# PIC.net
KiCad netlist of a schematic drawn in Altium Designer
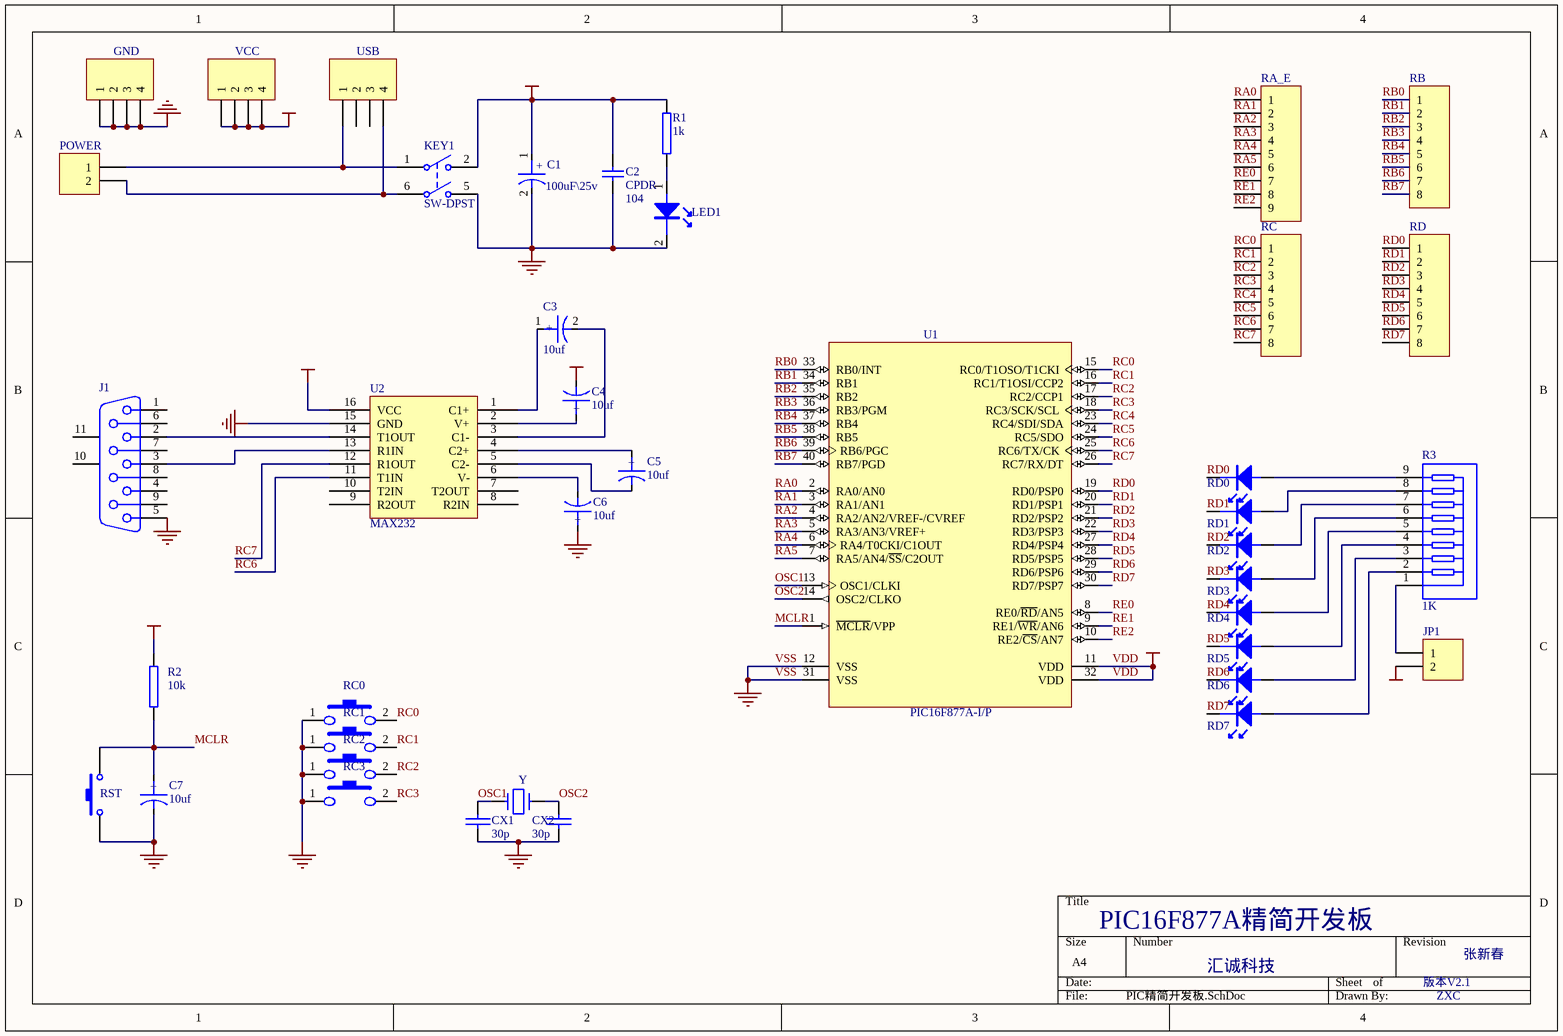
[diagram p0: PIC精简开发板.SchDoc]

(export (version "E")
  (design (tool "Eeschema 10.0.6"))
  (components
    (comp (ref "C1")
      (value "100u~{F}25v")
      (footprint "C-DJ-6")
      (description "Capacitor")
      (libsource (lib "OldCow1 (1)") (part "CAPACITOR POL"))
    )
    (comp (ref "C2")
      (value "CPDR")
      (footprint "CPDR")
      (description "瓷片电容")
      (fields (field (name "ALTIUM_VALUE") "104") (field (name "PUBLISHER") "Altium Limited"))
      (libsource (lib "zxcourhc") (part "CPDR"))
    )
    (comp (ref "C3")
      (value "10uf")
      (footprint "C-DJ-4")
      (description "Capacitor")
      (libsource (lib "") (part "CAPACITOR POL_1"))
    )
    (comp (ref "C4")
      (value "10uf")
      (footprint "C-DJ-4")
      (description "Capacitor")
      (libsource (lib "*") (part "CAPACITOR POL"))
    )
    (comp (ref "C5")
      (value "10uf")
      (footprint "C-DJ-4")
      (description "Capacitor")
      (libsource (lib "*") (part "CAPACITOR POL"))
    )
    (comp (ref "C6")
      (value "10uf")
      (footprint "C-DJ-4")
      (description "Capacitor")
      (libsource (lib "*") (part "CAPACITOR POL"))
    )
    (comp (ref "C7")
      (value "10uf")
      (footprint "C-DJ-4")
      (description "Capacitor")
      (libsource (lib "*") (part "CAPACITOR POL"))
    )
    (comp (ref "CX1")
      (value "30p")
      (footprint "HDR1X2")
      (description "Capacitor")
      (libsource (lib "*") (part "CAP"))
    )
    (comp (ref "CX2")
      (value "30p")
      (footprint "HDR1X2")
      (description "Capacitor")
      (libsource (lib "*") (part "CAP"))
    )
    (comp (ref "GND")
      (value "~")
      (footprint "HDR1X4")
      (description "Header, 4-Pin")
      (fields (field (name "PUBLISHER") "Altium Limited"))
      (libsource (lib "Miscellaneous Connectors") (part "Header 4"))
    )
    (comp (ref "J1")
      (value "D Connector 9")
      (footprint "DSUB1.385-2H9")
      (description "Receptacle Assembly, 9 Position, Right Angle")
      (fields (field (name "PUBLISHER") "Altium Limited"))
      (libsource (lib "Miscellaneous Connectors") (part "D Connector 9"))
    )
    (comp (ref "JP1")
      (value "~")
      (footprint "HDR1X2")
      (description "Header, 2-Pin")
      (fields (field (name "PUBLISHER") "Altium Limited"))
      (libsource (lib "") (part "Header 2_1"))
    )
    (comp (ref "KEY1")
      (value "SW-DPST")
      (footprint "DPDT-6")
      (description "Double-Pole, Single-Throw Switch")
      (fields (field (name "PUBLISHER") "Altium Limited"))
      (libsource (lib "Miscellaneous Devices") (part "SW-DPST"))
    )
    (comp (ref "LED1") (value "LED") (footprint "LED") (libsource (lib "") (part "LED_1")))
    (comp (ref "POWER")
      (value "~")
      (footprint "JK128_2")
      (description "Header, 2-Pin")
      (fields (field (name "PUBLISHER") "Altium Limited"))
      (libsource (lib "Miscellaneous Connectors") (part "Header 2"))
    )
    (comp (ref "R1") (value "1k") (footprint "RSE") (libsource (lib "*") (part "RES2")))
    (comp (ref "R2") (value "10k") (footprint "RSE") (libsource (lib "*") (part "RES2")))
    (comp (ref "R3")
      (value "1K")
      (footprint "HDR-10")
      (description "8位排阻")
      (fields (field (name "PUBLISHER") "Altium Limited"))
      (libsource (lib "zxcourhc") (part "Res PZ_8"))
    )
    (comp (ref "RA_E")
      (value "~")
      (footprint "HDR-9")
      (description "排针——9")
      (fields (field (name "PUBLISHER") "Altium Limited"))
      (libsource (lib "zxcourhc") (part "PZ_9"))
    )
    (comp (ref "RB")
      (value "~")
      (footprint "HDR-8")
      (description "排针——8")
      (fields (field (name "PUBLISHER") "Altium Limited"))
      (libsource (lib "zxcourhc") (part "PZ_8"))
    )
    (comp (ref "RC")
      (value "~")
      (footprint "HDR-8")
      (description "排针——8")
      (fields (field (name "PUBLISHER") "Altium Limited"))
      (libsource (lib "zxcourhc") (part "PZ_8"))
    )
    (comp (ref "RC0") (value "key1") (footprint "an-6*6") (libsource (lib "OldCow1 (1)") (part "key")))
    (comp (ref "RC1") (value "key2") (footprint "an-6*6") (libsource (lib "OldCow1 (1)") (part "key")))
    (comp (ref "RC2") (value "key3") (footprint "an-6*6") (libsource (lib "OldCow1 (1)") (part "key")))
    (comp (ref "RC3") (value "key4") (footprint "an-6*6") (libsource (lib "OldCow1 (1)") (part "key")))
    (comp (ref "RD")
      (value "~")
      (footprint "HDR-8")
      (description "排针——8")
      (fields (field (name "PUBLISHER") "Altium Limited"))
      (libsource (lib "zxcourhc") (part "PZ_8"))
    )
    (comp (ref "RD0") (value "LED") (footprint "LED_D") (libsource (lib "OldCow1 (1)") (part "LED")))
    (comp (ref "RD1") (value "LED") (footprint "LED_D") (libsource (lib "OldCow1 (1)") (part "LED")))
    (comp (ref "RD2") (value "LED") (footprint "LED_D") (libsource (lib "OldCow1 (1)") (part "LED")))
    (comp (ref "RD3") (value "LED") (footprint "LED_D") (libsource (lib "OldCow1 (1)") (part "LED")))
    (comp (ref "RD4") (value "LED") (footprint "LED_D") (libsource (lib "OldCow1 (1)") (part "LED")))
    (comp (ref "RD5") (value "LED") (footprint "LED_D") (libsource (lib "OldCow1 (1)") (part "LED")))
    (comp (ref "RD6") (value "LED") (footprint "LED_D") (libsource (lib "OldCow1 (1)") (part "LED")))
    (comp (ref "RD7") (value "LED") (footprint "LED_D") (libsource (lib "OldCow1 (1)") (part "LED")))
    (comp (ref "RST")
      (value "~")
      (footprint "an-6*6")
      (description "Switch")
      (fields (field (name "PUBLISHER") "Altium Limited"))
      (libsource (lib "Miscellaneous Devices") (part "SW-PB"))
    )
    (comp (ref "U1")
      (value "PIC16F877A-I/P")
      (footprint "AT89S52Pid")
      (fields (field (name "PUBLISHER") "Altium Limited"))
      (libsource (lib "Microchip Microcontroller 8-Bit PIC16F") (part "PIC16F877A-I/P"))
    )
    (comp (ref "U2") (value "MAX232") (footprint "DIP16") (libsource (lib "*") (part "MAX232")))
    (comp (ref "USB")
      (value "~")
      (footprint "USB-5V")
      (description "Header, 4-Pin")
      (fields (field (name "PUBLISHER") "Altium Limited"))
      (libsource (lib "Miscellaneous Connectors") (part "Header 4"))
    )
    (comp (ref "VCC")
      (value "~")
      (footprint "HDR1X4")
      (description "Header, 4-Pin")
      (fields (field (name "PUBLISHER") "Altium Limited"))
      (libsource (lib "Miscellaneous Connectors") (part "Header 4"))
    )
    (comp (ref "Y1")
      (value "Y")
      (footprint "JZ_ZC")
      (description "Crystal")
      (libsource (lib "*") (part "CRYSTAL"))
    )
  )
  (nets
    (net (code "1") (name "/MCLR") (class "Default")
      (node (ref "C7") (pin "1") (pinfunction "1_1") (pintype "passive"))
      (node (ref "R2") (pin "1") (pinfunction "1_1") (pintype "passive"))
      (node (ref "RST") (pin "1") (pinfunction "1_1") (pintype "passive"))
      (node (ref "U1") (pin "1") (pinfunction "~{MCLR}/VPP_1") (pintype "input"))
    )
    (net (code "2") (name "/OSC1") (class "Default")
      (node (ref "CX1") (pin "1") (pinfunction "1_1") (pintype "passive"))
      (node (ref "U1") (pin "13") (pinfunction "OSC1/CLKI_13") (pintype "input"))
      (node (ref "Y1") (pin "2") (pinfunction "2_2") (pintype "passive"))
    )
    (net (code "3") (name "/OSC2") (class "Default")
      (node (ref "CX2") (pin "1") (pinfunction "1_1") (pintype "passive"))
      (node (ref "U1") (pin "14") (pinfunction "OSC2/CLKO_14") (pintype "output"))
      (node (ref "Y1") (pin "1") (pinfunction "1_1") (pintype "passive"))
    )
    (net (code "4") (name "/RA0") (class "Default")
      (node (ref "RA_E") (pin "1") (pinfunction "1_1") (pintype "passive"))
      (node (ref "U1") (pin "2") (pinfunction "RA0/AN0_2") (pintype "bidirectional"))
    )
    (net (code "5") (name "/RA1") (class "Default")
      (node (ref "RA_E") (pin "2") (pinfunction "2_2") (pintype "passive"))
      (node (ref "U1") (pin "3") (pinfunction "RA1/AN1_3") (pintype "bidirectional"))
    )
    (net (code "6") (name "/RA2") (class "Default")
      (node (ref "RA_E") (pin "3") (pinfunction "3_3") (pintype "passive"))
      (node (ref "U1") (pin "4") (pinfunction "RA2/AN2/VREF-/CVREF_4") (pintype "bidirectional"))
    )
    (net (code "7") (name "/RA3") (class "Default")
      (node (ref "RA_E") (pin "4") (pinfunction "4_4") (pintype "passive"))
      (node (ref "U1") (pin "5") (pinfunction "RA3/AN3/VREF+_5") (pintype "bidirectional"))
    )
    (net (code "8") (name "/RA4") (class "Default")
      (node (ref "RA_E") (pin "5") (pinfunction "5_5") (pintype "passive"))
      (node (ref "U1") (pin "6") (pinfunction "RA4/T0CKI/C1OUT_6") (pintype "bidirectional"))
    )
    (net (code "9") (name "/RA5") (class "Default")
      (node (ref "RA_E") (pin "6") (pinfunction "6_6") (pintype "passive"))
      (node (ref "U1") (pin "7") (pinfunction "RA5/AN4/~{SS}/C2OUT_7") (pintype "bidirectional"))
    )
    (net (code "10") (name "/RB0") (class "Default")
      (node (ref "RB") (pin "1") (pinfunction "1_1") (pintype "passive"))
      (node (ref "U1") (pin "33") (pinfunction "RB0/INT_33") (pintype "bidirectional"))
    )
    (net (code "11") (name "/RB1") (class "Default")
      (node (ref "RB") (pin "2") (pinfunction "2_2") (pintype "passive"))
      (node (ref "U1") (pin "34") (pinfunction "RB1_34") (pintype "bidirectional"))
    )
    (net (code "12") (name "/RB2") (class "Default")
      (node (ref "RB") (pin "3") (pinfunction "3_3") (pintype "passive"))
      (node (ref "U1") (pin "35") (pinfunction "RB2_35") (pintype "bidirectional"))
    )
    (net (code "13") (name "/RB3") (class "Default")
      (node (ref "RB") (pin "4") (pinfunction "4_4") (pintype "passive"))
      (node (ref "U1") (pin "36") (pinfunction "RB3/PGM_36") (pintype "bidirectional"))
    )
    (net (code "14") (name "/RB4") (class "Default")
      (node (ref "RB") (pin "5") (pinfunction "5_5") (pintype "passive"))
      (node (ref "U1") (pin "37") (pinfunction "RB4_37") (pintype "bidirectional"))
    )
    (net (code "15") (name "/RB5") (class "Default")
      (node (ref "RB") (pin "6") (pinfunction "6_6") (pintype "passive"))
      (node (ref "U1") (pin "38") (pinfunction "RB5_38") (pintype "bidirectional"))
    )
    (net (code "16") (name "/RB6") (class "Default")
      (node (ref "RB") (pin "7") (pinfunction "7_7") (pintype "passive"))
      (node (ref "U1") (pin "39") (pinfunction "RB6/PGC_39") (pintype "bidirectional"))
    )
    (net (code "17") (name "/RB7") (class "Default")
      (node (ref "RB") (pin "8") (pinfunction "8_8") (pintype "passive"))
      (node (ref "U1") (pin "40") (pinfunction "RB7/PGD_40") (pintype "bidirectional"))
    )
    (net (code "18") (name "/RC0") (class "Default")
      (node (ref "RC") (pin "1") (pinfunction "1_1") (pintype "passive"))
      (node (ref "RC0") (pin "2") (pinfunction "2_2") (pintype "passive"))
      (node (ref "U1") (pin "15") (pinfunction "RC0/T1OSO/T1CKI_15") (pintype "bidirectional"))
    )
    (net (code "19") (name "/RC1") (class "Default")
      (node (ref "RC") (pin "2") (pinfunction "2_2") (pintype "passive"))
      (node (ref "RC1") (pin "2") (pinfunction "2_2") (pintype "passive"))
      (node (ref "U1") (pin "16") (pinfunction "RC1/T1OSI/CCP2_16") (pintype "bidirectional"))
    )
    (net (code "20") (name "/RC2") (class "Default")
      (node (ref "RC") (pin "3") (pinfunction "3_3") (pintype "passive"))
      (node (ref "RC2") (pin "2") (pinfunction "2_2") (pintype "passive"))
      (node (ref "U1") (pin "17") (pinfunction "RC2/CCP1_17") (pintype "bidirectional"))
    )
    (net (code "21") (name "/RC3") (class "Default")
      (node (ref "RC") (pin "4") (pinfunction "4_4") (pintype "passive"))
      (node (ref "RC3") (pin "2") (pinfunction "2_2") (pintype "passive"))
      (node (ref "U1") (pin "18") (pinfunction "RC3/SCK/SCL_18") (pintype "bidirectional"))
    )
    (net (code "22") (name "/RC4") (class "Default")
      (node (ref "RC") (pin "5") (pinfunction "5_5") (pintype "passive"))
      (node (ref "U1") (pin "23") (pinfunction "RC4/SDI/SDA_23") (pintype "bidirectional"))
    )
    (net (code "23") (name "/RC5") (class "Default")
      (node (ref "RC") (pin "6") (pinfunction "6_6") (pintype "passive"))
      (node (ref "U1") (pin "24") (pinfunction "RC5/SDO_24") (pintype "bidirectional"))
    )
    (net (code "24") (name "/RC6") (class "Default")
      (node (ref "RC") (pin "7") (pinfunction "7_7") (pintype "passive"))
      (node (ref "U1") (pin "25") (pinfunction "RC6/TX/CK_25") (pintype "bidirectional"))
      (node (ref "U2") (pin "11") (pinfunction "T1IN_11") (pintype "passive"))
    )
    (net (code "25") (name "/RC7") (class "Default")
      (node (ref "RC") (pin "8") (pinfunction "8_8") (pintype "passive"))
      (node (ref "U1") (pin "26") (pinfunction "RC7/RX/DT_26") (pintype "bidirectional"))
      (node (ref "U2") (pin "12") (pinfunction "R1OUT_12") (pintype "passive"))
    )
    (net (code "26") (name "/RD0") (class "Default")
      (node (ref "RD") (pin "1") (pinfunction "1_1") (pintype "passive"))
      (node (ref "RD0") (pin "2") (pinfunction "K_2") (pintype "passive"))
      (node (ref "U1") (pin "19") (pinfunction "RD0/PSP0_19") (pintype "bidirectional"))
    )
    (net (code "27") (name "/RD1") (class "Default")
      (node (ref "RD") (pin "2") (pinfunction "2_2") (pintype "passive"))
      (node (ref "RD1") (pin "2") (pinfunction "K_2") (pintype "passive"))
      (node (ref "U1") (pin "20") (pinfunction "RD1/PSP1_20") (pintype "bidirectional"))
    )
    (net (code "28") (name "/RD2") (class "Default")
      (node (ref "RD") (pin "3") (pinfunction "3_3") (pintype "passive"))
      (node (ref "RD2") (pin "2") (pinfunction "K_2") (pintype "passive"))
      (node (ref "U1") (pin "21") (pinfunction "RD2/PSP2_21") (pintype "bidirectional"))
    )
    (net (code "29") (name "/RD3") (class "Default")
      (node (ref "RD") (pin "4") (pinfunction "4_4") (pintype "passive"))
      (node (ref "RD3") (pin "2") (pinfunction "K_2") (pintype "passive"))
      (node (ref "U1") (pin "22") (pinfunction "RD3/PSP3_22") (pintype "bidirectional"))
    )
    (net (code "30") (name "/RD4") (class "Default")
      (node (ref "RD") (pin "5") (pinfunction "5_5") (pintype "passive"))
      (node (ref "RD4") (pin "2") (pinfunction "K_2") (pintype "passive"))
      (node (ref "U1") (pin "27") (pinfunction "RD4/PSP4_27") (pintype "bidirectional"))
    )
    (net (code "31") (name "/RD5") (class "Default")
      (node (ref "RD") (pin "6") (pinfunction "6_6") (pintype "passive"))
      (node (ref "RD5") (pin "2") (pinfunction "K_2") (pintype "passive"))
      (node (ref "U1") (pin "28") (pinfunction "RD5/PSP5_28") (pintype "bidirectional"))
    )
    (net (code "32") (name "/RD6") (class "Default")
      (node (ref "RD") (pin "7") (pinfunction "7_7") (pintype "passive"))
      (node (ref "RD6") (pin "2") (pinfunction "K_2") (pintype "passive"))
      (node (ref "U1") (pin "29") (pinfunction "RD6/PSP6_29") (pintype "bidirectional"))
    )
    (net (code "33") (name "/RD7") (class "Default")
      (node (ref "RD") (pin "8") (pinfunction "8_8") (pintype "passive"))
      (node (ref "RD7") (pin "2") (pinfunction "K_2") (pintype "passive"))
      (node (ref "U1") (pin "30") (pinfunction "RD7/PSP7_30") (pintype "bidirectional"))
    )
    (net (code "34") (name "/RE0") (class "Default")
      (node (ref "RA_E") (pin "7") (pinfunction "7_7") (pintype "passive"))
      (node (ref "U1") (pin "8") (pinfunction "RE0/~{RD}/AN5_8") (pintype "bidirectional"))
    )
    (net (code "35") (name "/RE1") (class "Default")
      (node (ref "RA_E") (pin "8") (pinfunction "8_8") (pintype "passive"))
      (node (ref "U1") (pin "9") (pinfunction "RE1/~{WR}/AN6_9") (pintype "bidirectional"))
    )
    (net (code "36") (name "/RE2") (class "Default")
      (node (ref "RA_E") (pin "9") (pinfunction "9_9") (pintype "passive"))
      (node (ref "U1") (pin "10") (pinfunction "RE2/~{CS}/AN7_10") (pintype "bidirectional"))
    )
    (net (code "37") (name "GND") (class "Default")
      (node (ref "C1") (pin "2") (pinfunction "2_2") (pintype "passive"))
      (node (ref "C2") (pin "1") (pinfunction "1_1") (pintype "passive"))
      (node (ref "C6") (pin "1") (pinfunction "1_1") (pintype "passive"))
      (node (ref "C7") (pin "2") (pinfunction "2_2") (pintype "passive"))
      (node (ref "CX1") (pin "2") (pinfunction "2_2") (pintype "passive"))
      (node (ref "CX2") (pin "2") (pinfunction "2_2") (pintype "passive"))
      (node (ref "GND") (pin "1") (pinfunction "1_1") (pintype "passive"))
      (node (ref "GND") (pin "2") (pinfunction "2_2") (pintype "passive"))
      (node (ref "GND") (pin "3") (pinfunction "3_3") (pintype "passive"))
      (node (ref "GND") (pin "4") (pinfunction "4_4") (pintype "passive"))
      (node (ref "J1") (pin "5") (pinfunction "5_5") (pintype "passive"))
      (node (ref "KEY1") (pin "5") (pinfunction "NO2_5") (pintype "passive"))
      (node (ref "LED1") (pin "2") (pinfunction "K_2") (pintype "passive"))
      (node (ref "RC0") (pin "1") (pinfunction "1_1") (pintype "passive"))
      (node (ref "RC1") (pin "1") (pinfunction "1_1") (pintype "passive"))
      (node (ref "RC2") (pin "1") (pinfunction "1_1") (pintype "passive"))
      (node (ref "RC3") (pin "1") (pinfunction "1_1") (pintype "passive"))
      (node (ref "RST") (pin "2") (pinfunction "2_2") (pintype "passive"))
      (node (ref "U1") (pin "12") (pinfunction "VSS_12") (pintype "power_in"))
      (node (ref "U1") (pin "31") (pinfunction "VSS_31") (pintype "power_in"))
      (node (ref "U2") (pin "15") (pinfunction "GND_15") (pintype "passive"))
    )
    (net (code "38") (name "Net-(JP1-Pad1)") (class "Default")
      (node (ref "JP1") (pin "1") (pinfunction "1_1") (pintype "passive"))
      (node (ref "R3") (pin "1") (pinfunction "1_1") (pintype "passive"))
    )
    (net (code "39") (name "Net-(KEY1-COMMON1)") (class "Default")
      (node (ref "KEY1") (pin "1") (pinfunction "COMMON1_1") (pintype "passive"))
      (node (ref "POWER") (pin "1") (pinfunction "1_1") (pintype "passive"))
      (node (ref "USB") (pin "1") (pinfunction "1_1") (pintype "passive"))
    )
    (net (code "40") (name "Net-(KEY1-COMMON2)") (class "Default")
      (node (ref "KEY1") (pin "6") (pinfunction "COMMON2_6") (pintype "passive"))
      (node (ref "POWER") (pin "2") (pinfunction "2_2") (pintype "passive"))
      (node (ref "USB") (pin "4") (pinfunction "4_4") (pintype "passive"))
    )
    (net (code "41") (name "Net-(LED1-A)") (class "Default")
      (node (ref "LED1") (pin "1") (pinfunction "A_1") (pintype "passive"))
      (node (ref "R1") (pin "2") (pinfunction "2_2") (pintype "passive"))
    )
    (net (code "42") (name "Net-(RD0-A)") (class "Default")
      (node (ref "R3") (pin "9") (pinfunction "9_9") (pintype "passive"))
      (node (ref "RD0") (pin "1") (pinfunction "A_1") (pintype "passive"))
    )
    (net (code "43") (name "Net-(RD1-A)") (class "Default")
      (node (ref "R3") (pin "8") (pinfunction "8_8") (pintype "passive"))
      (node (ref "RD1") (pin "1") (pinfunction "A_1") (pintype "passive"))
    )
    (net (code "44") (name "Net-(RD2-A)") (class "Default")
      (node (ref "R3") (pin "7") (pinfunction "7_7") (pintype "passive"))
      (node (ref "RD2") (pin "1") (pinfunction "A_1") (pintype "passive"))
    )
    (net (code "45") (name "Net-(RD3-A)") (class "Default")
      (node (ref "R3") (pin "6") (pinfunction "6_6") (pintype "passive"))
      (node (ref "RD3") (pin "1") (pinfunction "A_1") (pintype "passive"))
    )
    (net (code "46") (name "Net-(RD4-A)") (class "Default")
      (node (ref "R3") (pin "5") (pinfunction "5_5") (pintype "passive"))
      (node (ref "RD4") (pin "1") (pinfunction "A_1") (pintype "passive"))
    )
    (net (code "47") (name "Net-(RD5-A)") (class "Default")
      (node (ref "R3") (pin "4") (pinfunction "4_4") (pintype "passive"))
      (node (ref "RD5") (pin "1") (pinfunction "A_1") (pintype "passive"))
    )
    (net (code "48") (name "Net-(RD6-A)") (class "Default")
      (node (ref "R3") (pin "3") (pinfunction "3_3") (pintype "passive"))
      (node (ref "RD6") (pin "1") (pinfunction "A_1") (pintype "passive"))
    )
    (net (code "49") (name "Net-(RD7-A)") (class "Default")
      (node (ref "R3") (pin "2") (pinfunction "2_2") (pintype "passive"))
      (node (ref "RD7") (pin "1") (pinfunction "A_1") (pintype "passive"))
    )
    (net (code "50") (name "Net-(U2-C1+)") (class "Default")
      (node (ref "C3") (pin "1") (pinfunction "1_1") (pintype "passive"))
      (node (ref "U2") (pin "1") (pinfunction "C1+_1") (pintype "passive"))
    )
    (net (code "51") (name "Net-(U2-C1-)") (class "Default")
      (node (ref "C3") (pin "2") (pinfunction "2_2") (pintype "passive"))
      (node (ref "U2") (pin "3") (pinfunction "C1-_3") (pintype "passive"))
    )
    (net (code "52") (name "Net-(U2-C2+)") (class "Default")
      (node (ref "C5") (pin "1") (pinfunction "1_1") (pintype "passive"))
      (node (ref "U2") (pin "4") (pinfunction "C2+_4") (pintype "passive"))
    )
    (net (code "53") (name "Net-(U2-C2-)") (class "Default")
      (node (ref "C5") (pin "2") (pinfunction "2_2") (pintype "passive"))
      (node (ref "U2") (pin "5") (pinfunction "C2-_5") (pintype "passive"))
    )
    (net (code "54") (name "Net-(U2-R1IN)") (class "Default")
      (node (ref "J1") (pin "3") (pinfunction "3_3") (pintype "passive"))
      (node (ref "U2") (pin "13") (pinfunction "R1IN_13") (pintype "passive"))
    )
    (net (code "55") (name "Net-(U2-T1OUT)") (class "Default")
      (node (ref "J1") (pin "2") (pinfunction "2_2") (pintype "passive"))
      (node (ref "U2") (pin "14") (pinfunction "T1OUT_14") (pintype "passive"))
    )
    (net (code "56") (name "Net-(U2-V+)") (class "Default")
      (node (ref "C4") (pin "1") (pinfunction "1_1") (pintype "passive"))
      (node (ref "U2") (pin "2") (pinfunction "V+_2") (pintype "passive"))
    )
    (net (code "57") (name "Net-(U2-V-)") (class "Default")
      (node (ref "C6") (pin "2") (pinfunction "2_2") (pintype "passive"))
      (node (ref "U2") (pin "6") (pinfunction "V-_6") (pintype "passive"))
    )
    (net (code "58") (name "VCC") (class "Default")
      (node (ref "C1") (pin "1") (pinfunction "1_1") (pintype "passive"))
      (node (ref "C2") (pin "2") (pinfunction "2_2") (pintype "passive"))
      (node (ref "C4") (pin "2") (pinfunction "2_2") (pintype "passive"))
      (node (ref "JP1") (pin "2") (pinfunction "2_2") (pintype "passive"))
      (node (ref "KEY1") (pin "2") (pinfunction "NO1_2") (pintype "passive"))
      (node (ref "R1") (pin "1") (pinfunction "1_1") (pintype "passive"))
      (node (ref "R2") (pin "2") (pinfunction "2_2") (pintype "passive"))
      (node (ref "U1") (pin "11") (pinfunction "VDD_11") (pintype "power_in"))
      (node (ref "U1") (pin "32") (pinfunction "VDD_32") (pintype "power_in"))
      (node (ref "U2") (pin "16") (pinfunction "VCC_16") (pintype "passive"))
      (node (ref "VCC") (pin "1") (pinfunction "1_1") (pintype "passive"))
      (node (ref "VCC") (pin "2") (pinfunction "2_2") (pintype "passive"))
      (node (ref "VCC") (pin "3") (pinfunction "3_3") (pintype "passive"))
      (node (ref "VCC") (pin "4") (pinfunction "4_4") (pintype "passive"))
    )
    (net (code "59") (name "unconnected-(J1-MH1-Pad10)") (class "Default")
      (node (ref "J1") (pin "10") (pinfunction "MH1_10") (pintype "passive"))
    )
    (net (code "60") (name "unconnected-(J1-MH2-Pad11)") (class "Default")
      (node (ref "J1") (pin "11") (pinfunction "MH2_11") (pintype "passive"))
    )
    (net (code "61") (name "unconnected-(J1-Pad1)") (class "Default")
      (node (ref "J1") (pin "1") (pinfunction "1_1") (pintype "passive"))
    )
    (net (code "62") (name "unconnected-(J1-Pad4)") (class "Default")
      (node (ref "J1") (pin "4") (pinfunction "4_4") (pintype "passive"))
    )
    (net (code "63") (name "unconnected-(J1-Pad6)") (class "Default")
      (node (ref "J1") (pin "6") (pinfunction "6_6") (pintype "passive"))
    )
    (net (code "64") (name "unconnected-(J1-Pad7)") (class "Default")
      (node (ref "J1") (pin "7") (pinfunction "7_7") (pintype "passive"))
    )
    (net (code "65") (name "unconnected-(J1-Pad8)") (class "Default")
      (node (ref "J1") (pin "8") (pinfunction "8_8") (pintype "passive"))
    )
    (net (code "66") (name "unconnected-(J1-Pad9)") (class "Default")
      (node (ref "J1") (pin "9") (pinfunction "9_9") (pintype "passive"))
    )
    (net (code "67") (name "unconnected-(U2-R2IN-Pad8)") (class "Default")
      (node (ref "U2") (pin "8") (pinfunction "R2IN_8") (pintype "passive"))
    )
    (net (code "68") (name "unconnected-(U2-R2OUT-Pad9)") (class "Default")
      (node (ref "U2") (pin "9") (pinfunction "R2OUT_9") (pintype "passive"))
    )
    (net (code "69") (name "unconnected-(U2-T2IN-Pad10)") (class "Default")
      (node (ref "U2") (pin "10") (pinfunction "T2IN_10") (pintype "passive"))
    )
    (net (code "70") (name "unconnected-(U2-T2OUT-Pad7)") (class "Default")
      (node (ref "U2") (pin "7") (pinfunction "T2OUT_7") (pintype "passive"))
    )
    (net (code "71") (name "unconnected-(USB-Pad2)") (class "Default")
      (node (ref "USB") (pin "2") (pinfunction "2_2") (pintype "passive"))
    )
    (net (code "72") (name "unconnected-(USB-Pad3)") (class "Default")
      (node (ref "USB") (pin "3") (pinfunction "3_3") (pintype "passive"))
    )
  )
)
